# Microcontroller.net
KiCad netlist of a schematic drawn in Altium Designer
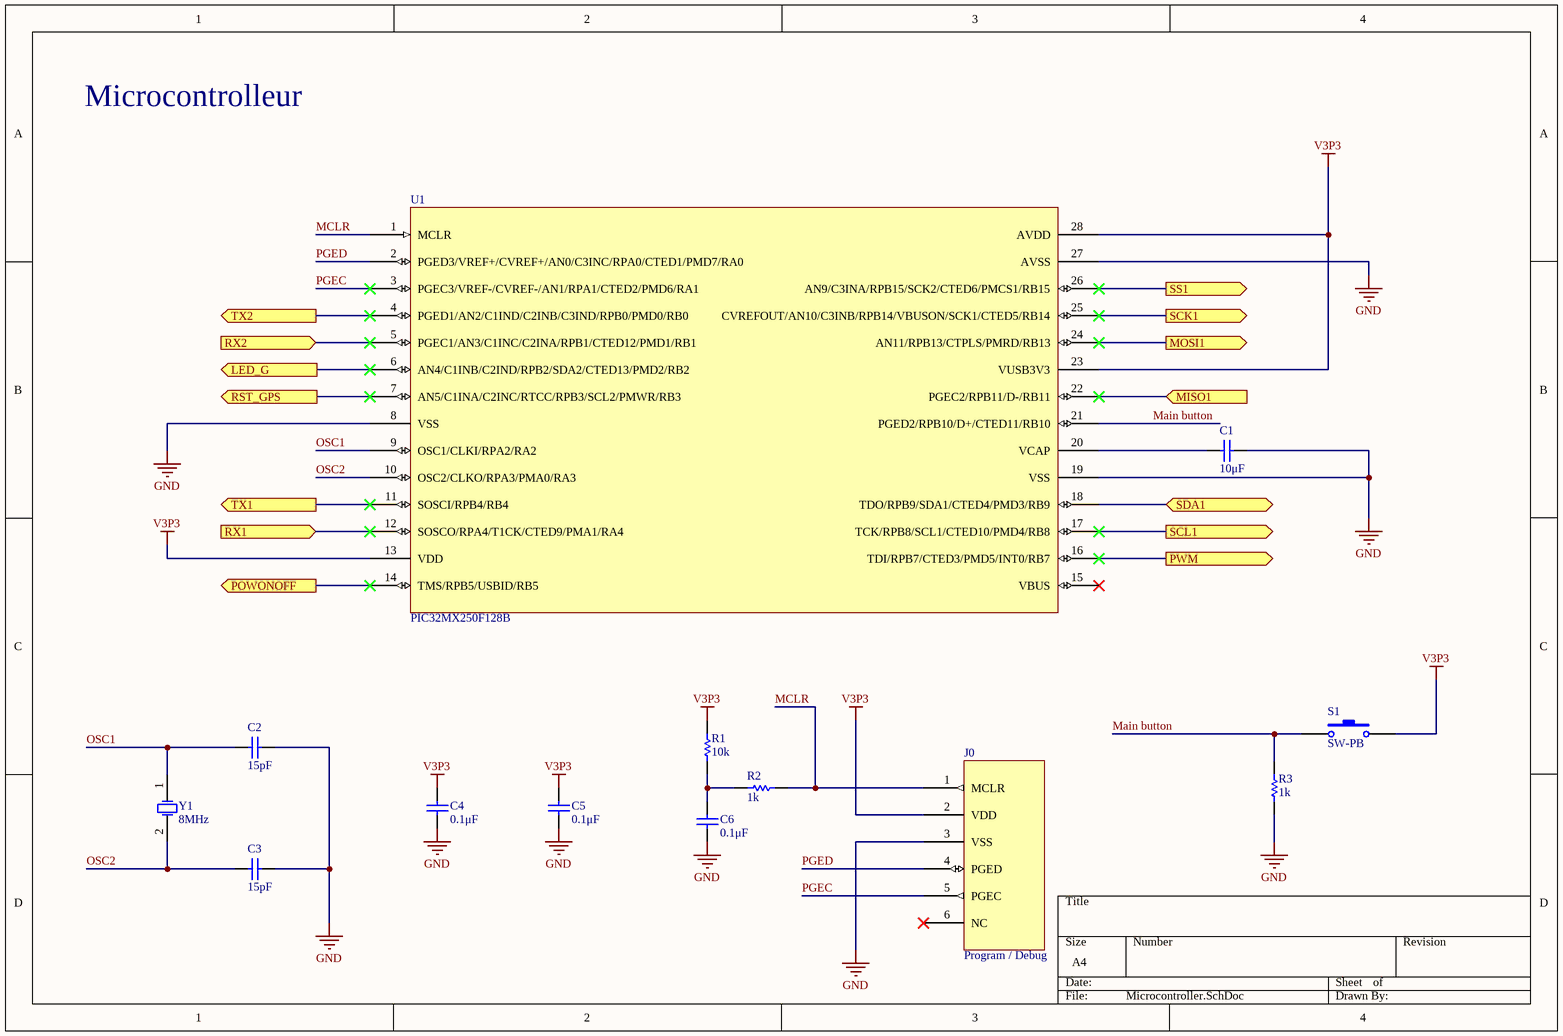
[diagram p0: Microcontroller.SchDoc]

(export (version "E")
  (design (tool "Eeschema 10.0.6"))
  (components
    (comp (ref "C1")
      (value "10μF")
      (footprint "own_0603")
      (description "Capacitor")
      (fields (field (name "PUBLISHER") "Altium Limited"))
      (libsource (lib "Miscellaneous Devices") (part "Cap"))
    )
    (comp (ref "C2")
      (value "15pF")
      (footprint "own_0603")
      (description "Capacitor")
      (fields (field (name "PUBLISHER") "Altium Limited"))
      (libsource (lib "Miscellaneous Devices") (part "Cap"))
    )
    (comp (ref "C3")
      (value "15pF")
      (footprint "own_0603")
      (description "Capacitor")
      (fields (field (name "PUBLISHER") "Altium Limited"))
      (libsource (lib "Miscellaneous Devices") (part "Cap"))
    )
    (comp (ref "C4")
      (value "0.1μF")
      (footprint "own_0603")
      (description "Capacitor")
      (fields (field (name "PUBLISHER") "Altium Limited"))
      (libsource (lib "Miscellaneous Devices") (part "Cap"))
    )
    (comp (ref "C5")
      (value "0.1μF")
      (footprint "own_0603")
      (description "Capacitor")
      (fields (field (name "PUBLISHER") "Altium Limited"))
      (libsource (lib "Miscellaneous Devices") (part "Cap"))
    )
    (comp (ref "C6")
      (value "0.1μF")
      (footprint "own_0603")
      (description "Capacitor")
      (fields (field (name "PUBLISHER") "Altium Limited"))
      (libsource (lib "Miscellaneous Devices") (part "Cap"))
    )
    (comp (ref "J0")
      (value "Program / Debug")
      (footprint "C-Grid III X6")
      (libsource (lib "Schlib") (part "ICSP"))
    )
    (comp (ref "R1")
      (value "10k")
      (footprint "own_0603")
      (description "Resistor")
      (fields (field (name "PUBLISHER") "Altium Limited"))
      (libsource (lib "Miscellaneous Devices") (part "Res1"))
    )
    (comp (ref "R2")
      (value "1k")
      (footprint "own_0603")
      (description "Resistor")
      (fields (field (name "PUBLISHER") "Altium Limited"))
      (libsource (lib "Miscellaneous Devices") (part "Res1"))
    )
    (comp (ref "R3")
      (value "1k")
      (footprint "own_0603")
      (description "Resistor")
      (fields (field (name "PUBLISHER") "Altium Limited"))
      (libsource (lib "Miscellaneous Devices") (part "Res1"))
    )
    (comp (ref "S1")
      (value "SW-PB")
      (footprint "SPST-2")
      (description "Switch")
      (libsource (lib "Miscellaneous Devices") (part "SW-PB"))
    )
    (comp (ref "U1")
      (value "PIC32MX250F128B")
      (footprint "PIC32MX250F128/SO")
      (description "Microcontrolleur")
      (libsource (lib "Schlib") (part "PIC32MX250F128B"))
    )
    (comp (ref "Y1")
      (value "8MHz")
      (footprint "9B-8.000MAAJ-B")
      (description "Crystal Oscillator")
      (libsource (lib "Miscellaneous Devices") (part "XTAL"))
    )
  )
  (nets
    (net (code "1") (name "/LED_G") (class "Default")
      (node (ref "U1") (pin "6") (pinfunction "AN4/C1INB/C2IND/RPB2/SDA2/CTED13/PMD2/RB2_6") (pintype "bidirectional+no_connect"))
    )
    (net (code "2") (name "/MCLR") (class "Default")
      (node (ref "J0") (pin "1") (pinfunction "MCLR_1") (pintype "output"))
      (node (ref "R2") (pin "1") (pinfunction "1_1") (pintype "passive"))
      (node (ref "U1") (pin "1") (pinfunction "MCLR_1") (pintype "input"))
    )
    (net (code "3") (name "/MISO1") (class "Default")
      (node (ref "U1") (pin "22") (pinfunction "PGEC2/RPB11/D-/RB11_22") (pintype "bidirectional+no_connect"))
    )
    (net (code "4") (name "/MOSI1") (class "Default")
      (node (ref "U1") (pin "24") (pinfunction "AN11/RPB13/CTPLS/PMRD/RB13_24") (pintype "bidirectional+no_connect"))
    )
    (net (code "5") (name "/Main button") (class "Default")
      (node (ref "R3") (pin "1") (pinfunction "1_1") (pintype "passive"))
      (node (ref "S1") (pin "1") (pinfunction "1_1") (pintype "passive"))
      (node (ref "U1") (pin "21") (pinfunction "PGED2/RPB10/D+/CTED11/RB10_21") (pintype "bidirectional"))
    )
    (net (code "6") (name "/OSC1") (class "Default")
      (node (ref "C2") (pin "1") (pinfunction "1_1") (pintype "passive"))
      (node (ref "U1") (pin "9") (pinfunction "OSC1/CLKI/RPA2/RA2_9") (pintype "bidirectional"))
      (node (ref "Y1") (pin "1") (pinfunction "OSC1_1") (pintype "passive"))
    )
    (net (code "7") (name "/OSC2") (class "Default")
      (node (ref "C3") (pin "1") (pinfunction "1_1") (pintype "passive"))
      (node (ref "U1") (pin "10") (pinfunction "OSC2/CLKO/RPA3/PMA0/RA3_10") (pintype "bidirectional"))
      (node (ref "Y1") (pin "2") (pinfunction "OSC2_2") (pintype "passive"))
    )
    (net (code "8") (name "/PGEC") (class "Default")
      (node (ref "J0") (pin "5") (pinfunction "PGEC_5") (pintype "output"))
      (node (ref "U1") (pin "3") (pinfunction "PGEC3/VREF-/CVREF-/AN1/RPA1/CTED2/PMD6/RA1_3") (pintype "bidirectional"))
    )
    (net (code "9") (name "/PGED") (class "Default")
      (node (ref "J0") (pin "4") (pinfunction "PGED_4") (pintype "bidirectional"))
      (node (ref "U1") (pin "2") (pinfunction "PGED3/VREF+/CVREF+/AN0/C3INC/RPA0/CTED1/PMD7/RA0_2") (pintype "bidirectional"))
    )
    (net (code "10") (name "/POWONOFF") (class "Default")
      (node (ref "U1") (pin "14") (pinfunction "TMS/RPB5/USBID/RB5_14") (pintype "bidirectional+no_connect"))
    )
    (net (code "11") (name "/PWM") (class "Default")
      (node (ref "U1") (pin "16") (pinfunction "TDI/RPB7/CTED3/PMD5/INT0/RB7_16") (pintype "bidirectional+no_connect"))
    )
    (net (code "12") (name "/RST_GPS") (class "Default")
      (node (ref "U1") (pin "7") (pinfunction "AN5/C1INA/C2INC/RTCC/RPB3/SCL2/PMWR/RB3_7") (pintype "bidirectional+no_connect"))
    )
    (net (code "13") (name "/RX1") (class "Default")
      (node (ref "U1") (pin "12") (pinfunction "SOSCO/RPA4/T1CK/CTED9/PMA1/RA4_12") (pintype "bidirectional+no_connect"))
    )
    (net (code "14") (name "/RX2") (class "Default")
      (node (ref "U1") (pin "5") (pinfunction "PGEC1/AN3/C1INC/C2INA/RPB1/CTED12/PMD1/RB1_5") (pintype "bidirectional+no_connect"))
    )
    (net (code "15") (name "/SCK1") (class "Default")
      (node (ref "U1") (pin "25") (pinfunction "CVREFOUT/AN10/C3INB/RPB14/VBUSON/SCK1/CTED5/RB14_25") (pintype "bidirectional+no_connect"))
    )
    (net (code "16") (name "/SCL1") (class "Default")
      (node (ref "U1") (pin "17") (pinfunction "TCK/RPB8/SCL1/CTED10/PMD4/RB8_17") (pintype "bidirectional+no_connect"))
    )
    (net (code "17") (name "/SDA1") (class "Default")
      (node (ref "U1") (pin "18") (pinfunction "TDO/RPB9/SDA1/CTED4/PMD3/RB9_18") (pintype "bidirectional"))
    )
    (net (code "18") (name "/SS1") (class "Default")
      (node (ref "U1") (pin "26") (pinfunction "AN9/C3INA/RPB15/SCK2/CTED6/PMCS1/RB15_26") (pintype "bidirectional+no_connect"))
    )
    (net (code "19") (name "/TX1") (class "Default")
      (node (ref "U1") (pin "11") (pinfunction "SOSCI/RPB4/RB4_11") (pintype "bidirectional+no_connect"))
    )
    (net (code "20") (name "/TX2") (class "Default")
      (node (ref "U1") (pin "4") (pinfunction "PGED1/AN2/C1IND/C2INB/C3IND/RPB0/PMD0/RB0_4") (pintype "bidirectional+no_connect"))
    )
    (net (code "21") (name "GND") (class "Default")
      (node (ref "C1") (pin "1") (pinfunction "1_1") (pintype "passive"))
      (node (ref "C2") (pin "2") (pinfunction "2_2") (pintype "passive"))
      (node (ref "C3") (pin "2") (pinfunction "2_2") (pintype "passive"))
      (node (ref "C4") (pin "1") (pinfunction "1_1") (pintype "passive"))
      (node (ref "C5") (pin "1") (pinfunction "1_1") (pintype "passive"))
      (node (ref "C6") (pin "1") (pinfunction "1_1") (pintype "passive"))
      (node (ref "J0") (pin "3") (pinfunction "VSS_3") (pintype "power_in"))
      (node (ref "R3") (pin "2") (pinfunction "2_2") (pintype "passive"))
      (node (ref "U1") (pin "19") (pinfunction "VSS_19") (pintype "power_in"))
      (node (ref "U1") (pin "27") (pinfunction "AVSS_27") (pintype "power_in"))
      (node (ref "U1") (pin "8") (pinfunction "VSS_8") (pintype "power_in"))
    )
    (net (code "22") (name "Net-(C6-Pad2)") (class "Default")
      (node (ref "C6") (pin "2") (pinfunction "2_2") (pintype "passive"))
      (node (ref "R1") (pin "2") (pinfunction "2_2") (pintype "passive"))
      (node (ref "R2") (pin "2") (pinfunction "2_2") (pintype "passive"))
    )
    (net (code "23") (name "Net-(U1-VCAP)") (class "Default")
      (node (ref "C1") (pin "2") (pinfunction "2_2") (pintype "passive"))
      (node (ref "U1") (pin "20") (pinfunction "VCAP_20") (pintype "power_in"))
    )
    (net (code "24") (name "V3P3") (class "Default")
      (node (ref "C4") (pin "2") (pinfunction "2_2") (pintype "passive"))
      (node (ref "C5") (pin "2") (pinfunction "2_2") (pintype "passive"))
      (node (ref "J0") (pin "2") (pinfunction "VDD_2") (pintype "power_in"))
      (node (ref "R1") (pin "1") (pinfunction "1_1") (pintype "passive"))
      (node (ref "S1") (pin "2") (pinfunction "2_2") (pintype "passive"))
      (node (ref "U1") (pin "13") (pinfunction "VDD_13") (pintype "passive"))
      (node (ref "U1") (pin "23") (pinfunction "VUSB3V3_23") (pintype "power_in"))
      (node (ref "U1") (pin "28") (pinfunction "AVDD_28") (pintype "power_in"))
    )
    (net (code "25") (name "unconnected-(J0-NC-Pad6)") (class "Default")
      (node (ref "J0") (pin "6") (pinfunction "NC_6") (pintype "passive+no_connect"))
    )
    (net (code "26") (name "unconnected-(U1-VBUS-Pad15)") (class "Default")
      (node (ref "U1") (pin "15") (pinfunction "VBUS_15") (pintype "bidirectional+no_connect"))
    )
  )
)
